# P01_mpsm.net
KiCad netlist of a schematic drawn in Altium Designer
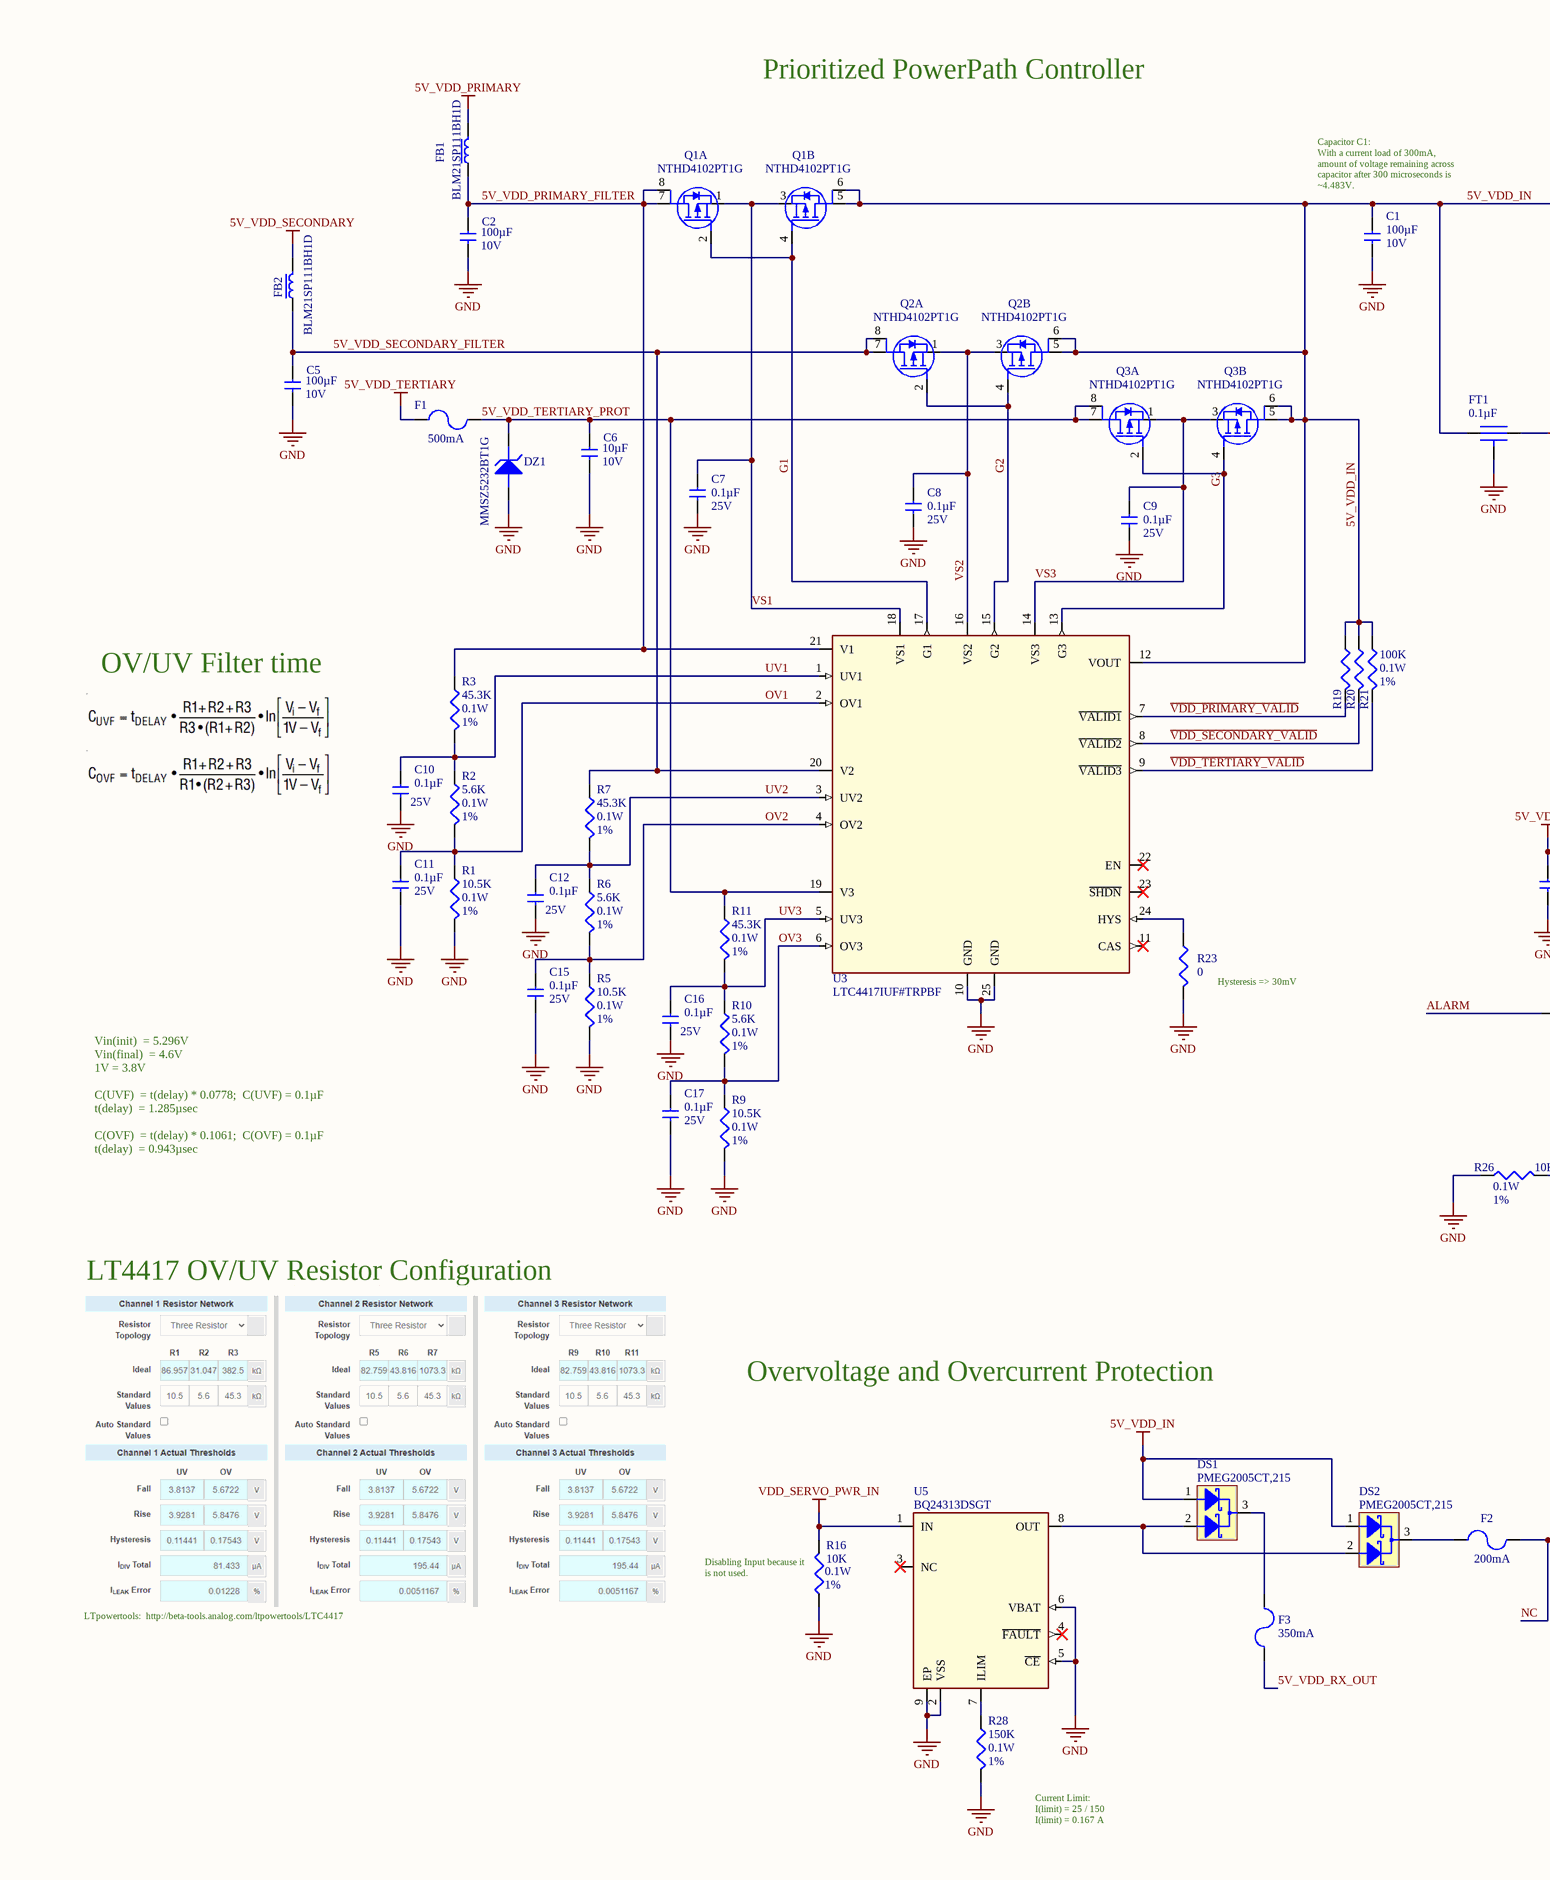
[diagram p0: P01_mpsm.SchDoc, left]
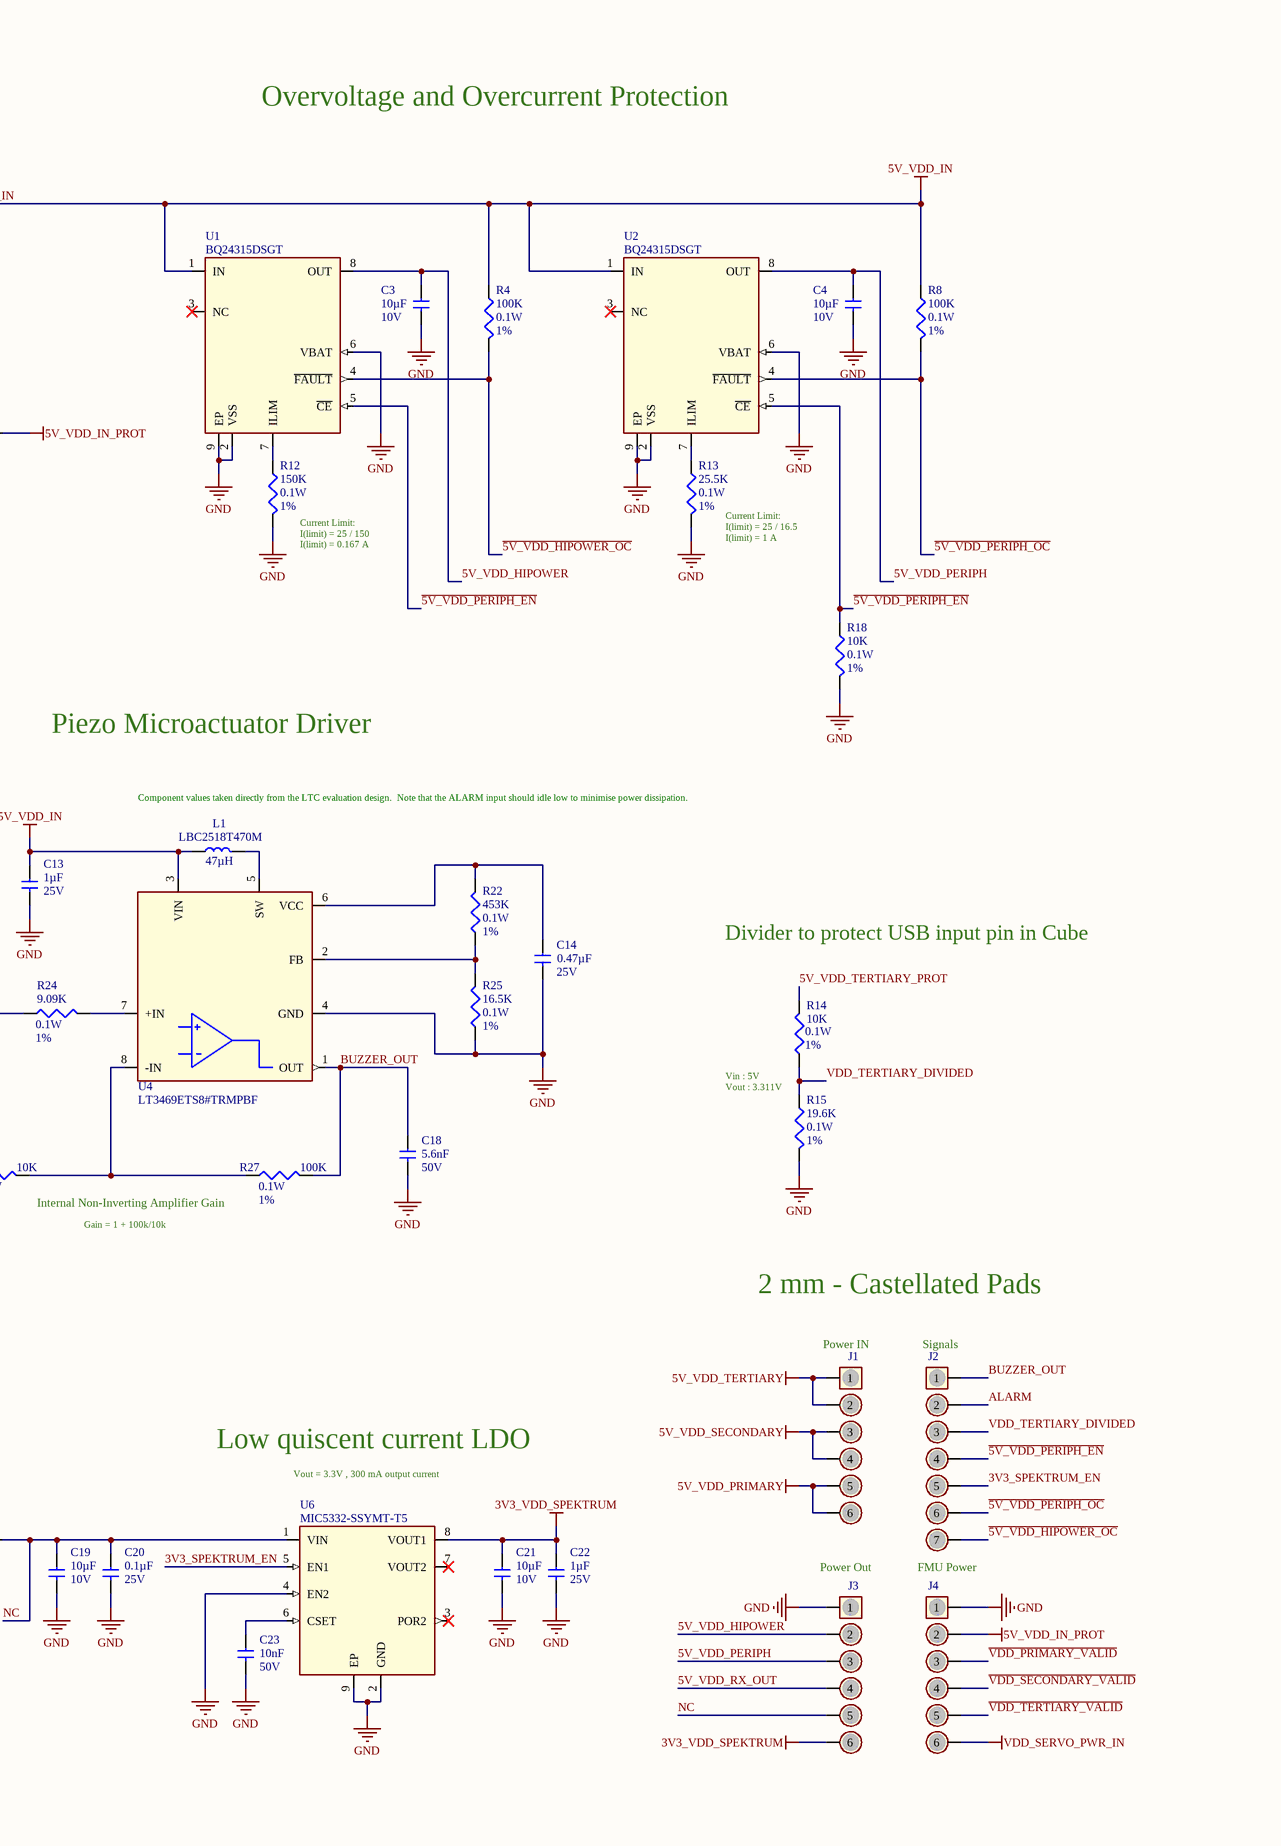
[diagram p1: P01_mpsm.SchDoc, right]

(export (version "E")
  (design (tool "Eeschema 10.0.6"))
  (components
    (comp (ref "C1")
      (value "100µF")
      (footprint "CC-1206")
      (fields
        (field (name "MFG") "TDK Corporation")
        (field (name "TOLERANCE") "20%")
        (field (name "VOLTAGE") "10V")
      )
      (libsource (lib "mpsm") (part "CC-100µF-X5R-10V-20%-1206"))
    )
    (comp (ref "C2")
      (value "100µF")
      (footprint "CC-1206")
      (fields
        (field (name "MFG") "TDK Corporation")
        (field (name "TOLERANCE") "20%")
        (field (name "VOLTAGE") "10V")
      )
      (libsource (lib "mpsm") (part "CC-100µF-X5R-10V-20%-1206"))
    )
    (comp (ref "C3")
      (value "10µF")
      (footprint "CC-0603")
      (fields
        (field (name "MFG") "Murata Electronics")
        (field (name "TOLERANCE") "10%")
        (field (name "VOLTAGE") "10V")
      )
      (libsource (lib "mpsm") (part "CC-10µF-X7T-10V-10%-0603"))
    )
    (comp (ref "C4")
      (value "10µF")
      (footprint "CC-0603")
      (fields
        (field (name "MFG") "Murata Electronics")
        (field (name "TOLERANCE") "10%")
        (field (name "VOLTAGE") "10V")
      )
      (libsource (lib "mpsm") (part "CC-10µF-X7T-10V-10%-0603"))
    )
    (comp (ref "C5")
      (value "100µF")
      (footprint "CC-1206")
      (fields
        (field (name "MFG") "TDK Corporation")
        (field (name "TOLERANCE") "20%")
        (field (name "VOLTAGE") "10V")
      )
      (libsource (lib "mpsm") (part "CC-100µF-X5R-10V-20%-1206"))
    )
    (comp (ref "C6")
      (value "10µF")
      (footprint "CC-0603")
      (fields
        (field (name "MFG") "Murata Electronics")
        (field (name "TOLERANCE") "10%")
        (field (name "VOLTAGE") "10V")
      )
      (libsource (lib "mpsm") (part "CC-10µF-X7T-10V-10%-0603"))
    )
    (comp (ref "C7")
      (value "0.1µF")
      (footprint "CC-0402")
      (fields
        (field (name "MFG") "Murata Electronics")
        (field (name "TOLERANCE") "10%")
        (field (name "VOLTAGE") "25V")
      )
      (libsource (lib "mpsm") (part "CC-0.1µF-X7R-25V-10%-0402"))
    )
    (comp (ref "C8")
      (value "0.1µF")
      (footprint "CC-0402")
      (fields
        (field (name "MFG") "Murata Electronics")
        (field (name "TOLERANCE") "10%")
        (field (name "VOLTAGE") "25V")
      )
      (libsource (lib "mpsm") (part "CC-0.1µF-X7R-25V-10%-0402"))
    )
    (comp (ref "C9")
      (value "0.1µF")
      (footprint "CC-0402")
      (fields
        (field (name "MFG") "Murata Electronics")
        (field (name "TOLERANCE") "10%")
        (field (name "VOLTAGE") "25V")
      )
      (libsource (lib "mpsm") (part "CC-0.1µF-X7R-25V-10%-0402"))
    )
    (comp (ref "C10")
      (value "0.1µF")
      (footprint "CC-0402")
      (fields
        (field (name "MFG") "Murata Electronics")
        (field (name "TOLERANCE") "10%")
        (field (name "VOLTAGE") "25V")
      )
      (libsource (lib "mpsm") (part "CC-0.1µF-X7R-25V-10%-0402"))
    )
    (comp (ref "C11")
      (value "0.1µF")
      (footprint "CC-0402")
      (fields
        (field (name "MFG") "Murata Electronics")
        (field (name "TOLERANCE") "10%")
        (field (name "VOLTAGE") "25V")
      )
      (libsource (lib "mpsm") (part "CC-0.1µF-X7R-25V-10%-0402"))
    )
    (comp (ref "C12")
      (value "0.1µF")
      (footprint "CC-0402")
      (fields
        (field (name "MFG") "Murata Electronics")
        (field (name "TOLERANCE") "10%")
        (field (name "VOLTAGE") "25V")
      )
      (libsource (lib "mpsm") (part "CC-0.1µF-X7R-25V-10%-0402"))
    )
    (comp (ref "C13")
      (value "1µF")
      (footprint "CC-0402")
      (fields
        (field (name "MFG") "Murata Electronics")
        (field (name "TOLERANCE") "10%")
        (field (name "VOLTAGE") "25V")
      )
      (libsource (lib "mpsm") (part "CC-1µF-X6S-25V-10%-0402"))
    )
    (comp (ref "C14")
      (value "0.47µF")
      (footprint "CC-0402")
      (fields
        (field (name "TOLERANCE") "±10%")
        (field (name "MFG") "Murata Electronics")
        (field (name "VOLTAGE") "25V")
      )
      (libsource (lib "mpsm") (part "CC-0.47µF-X5R-25V-10%-0402"))
    )
    (comp (ref "C15")
      (value "0.1µF")
      (footprint "CC-0402")
      (fields
        (field (name "MFG") "Murata Electronics")
        (field (name "TOLERANCE") "10%")
        (field (name "VOLTAGE") "25V")
      )
      (libsource (lib "mpsm") (part "CC-0.1µF-X7R-25V-10%-0402"))
    )
    (comp (ref "C16")
      (value "0.1µF")
      (footprint "CC-0402")
      (fields
        (field (name "MFG") "Murata Electronics")
        (field (name "TOLERANCE") "10%")
        (field (name "VOLTAGE") "25V")
      )
      (libsource (lib "mpsm") (part "CC-0.1µF-X7R-25V-10%-0402"))
    )
    (comp (ref "C17")
      (value "0.1µF")
      (footprint "CC-0402")
      (fields
        (field (name "MFG") "Murata Electronics")
        (field (name "TOLERANCE") "10%")
        (field (name "VOLTAGE") "25V")
      )
      (libsource (lib "mpsm") (part "CC-0.1µF-X7R-25V-10%-0402"))
    )
    (comp (ref "C18")
      (value "5.6nF")
      (footprint "CC-0402")
      (fields (field (name "TOLERANCE") "±10%") (field (name "MFG") "Yageo") (field (name "VOLTAGE") "50V"))
      (libsource (lib "mpsm") (part "CC-5.6nF-X7R-50V-5%-0402"))
    )
    (comp (ref "C19")
      (value "10µF")
      (footprint "CC-0603")
      (fields
        (field (name "MFG") "Murata Electronics")
        (field (name "TOLERANCE") "10%")
        (field (name "VOLTAGE") "10V")
      )
      (libsource (lib "mpsm") (part "CC-10µF-X7T-10V-10%-0603"))
    )
    (comp (ref "C20")
      (value "0.1µF")
      (footprint "CC-0402")
      (fields
        (field (name "MFG") "Murata Electronics")
        (field (name "TOLERANCE") "10%")
        (field (name "VOLTAGE") "25V")
      )
      (libsource (lib "mpsm") (part "CC-0.1µF-X7R-25V-10%-0402"))
    )
    (comp (ref "C21")
      (value "10µF")
      (footprint "CC-0603")
      (fields
        (field (name "MFG") "Murata Electronics")
        (field (name "TOLERANCE") "10%")
        (field (name "VOLTAGE") "10V")
      )
      (libsource (lib "mpsm") (part "CC-10µF-X7T-10V-10%-0603"))
    )
    (comp (ref "C22")
      (value "1µF")
      (footprint "CC-0402")
      (fields
        (field (name "MFG") "Murata Electronics")
        (field (name "TOLERANCE") "10%")
        (field (name "VOLTAGE") "25V")
      )
      (libsource (lib "mpsm") (part "CC-1µF-X6S-25V-10%-0402"))
    )
    (comp (ref "C23")
      (value "10nF")
      (footprint "CC-0402")
      (fields
        (field (name "TOLERANCE") "±10%")
        (field (name "MFG") "Murata Electronics")
        (field (name "VOLTAGE") "50V")
      )
      (libsource (lib "mpsm") (part "CC-10nF-X7R-50V-10%-0402"))
    )
    (comp (ref "DS1")
      (value "PMEG2005CT,215")
      (footprint "SOT-23-3")
      (fields (field (name "MFG") "Nexperia USA Inc."))
      (libsource (lib "mpsm") (part "DS-PMEG2005CT,215-SOT-23-3"))
    )
    (comp (ref "DS2")
      (value "PMEG2005CT,215")
      (footprint "SOT-23-3")
      (fields (field (name "MFG") "Nexperia USA Inc."))
      (libsource (lib "mpsm") (part "DS-PMEG2005CT,215-SOT-23-3"))
    )
    (comp (ref "DZ1")
      (value "MMSZ5232BT1G")
      (footprint "SOD-123")
      (fields (field (name "MFG") "ON Semiconductor"))
      (libsource (lib "mpsm") (part "DZ-5.6V-MMSZ5232BT1G-SOD-123"))
    )
    (comp (ref "F1")
      (value "500mA")
      (footprint "CF-0402")
      (fields (field (name "MFG") "BOURNS"))
      (libsource (lib "mpsm") (part "FUSE-500mA-32V-0402"))
    )
    (comp (ref "F2")
      (value "200mA")
      (footprint "CF-1206")
      (fields (field (name "MFG") "Bel Fuse Inc."))
      (libsource (lib "mpsm") (part "FUSE-200mA-20V-1206"))
    )
    (comp (ref "F3")
      (value "350mA")
      (footprint "CF-1206")
      (fields (field (name "MFG") "Littelfuse Inc."))
      (libsource (lib "mpsm") (part "FUSE-350mA-16V-1206"))
    )
    (comp (ref "FB1")
      (value "BLM21SP111BH1D")
      (footprint "FB-0805")
      (fields (field (name "MFG") "Murata Electronics"))
      (libsource (lib "mpsm") (part "FB-BLM21SP111BH1D-0805"))
    )
    (comp (ref "FB2")
      (value "BLM21SP111BH1D")
      (footprint "FB-0805")
      (fields (field (name "MFG") "Murata Electronics"))
      (libsource (lib "mpsm") (part "FB-BLM21SP111BH1D-0805"))
    )
    (comp (ref "FT1")
      (value "0.1µF")
      (footprint "CF-0603 - 3PC-PAD")
      (fields (field (name "MFG") "Murata Electronics"))
      (libsource (lib "mpsm") (part "CAP FT-0.1µF-X7R-16V-20%-0603"))
    )
    (comp (ref "J1")
      (value "6 Contacts")
      (footprint "1X06M")
      (fields
        (field (name "MANUFACTURER") "TE Connectivity Aerospace, Defense and Marine")
        (field (name "MANUFACTURER PART NUMBER") "205089-1")
      )
      (libsource (lib "mpsm") (part "6-Pin-Contact-PSM"))
    )
    (comp (ref "J2")
      (value "7 Contacts")
      (footprint "1X07M")
      (fields
        (field (name "MANUFACTURER") "TE Connectivity Aerospace, Defense and Marine")
        (field (name "MANUFACTURER PART NUMBER") "205089-1")
      )
      (libsource (lib "mpsm") (part "7-Pin-Contact-PSM"))
    )
    (comp (ref "J3")
      (value "6 Contacts")
      (footprint "1X06M")
      (fields
        (field (name "MANUFACTURER") "TE Connectivity Aerospace, Defense and Marine")
        (field (name "MANUFACTURER PART NUMBER") "205089-1")
      )
      (libsource (lib "mpsm") (part "6-Pin-Contact-PSM"))
    )
    (comp (ref "J4")
      (value "6 Contacts")
      (footprint "1X06M")
      (fields
        (field (name "MANUFACTURER") "TE Connectivity Aerospace, Defense and Marine")
        (field (name "MANUFACTURER PART NUMBER") "205089-1")
      )
      (libsource (lib "") (part "6-Pin-Contact-PSM_1"))
    )
    (comp (ref "L1")
      (value "LBC2518T470M")
      (footprint "IND-1007")
      (fields (field (name "MFG") "Taiyo Yuden") (field (name "INDUCTANCE") "47µH"))
      (libsource (lib "mpsm") (part "IND-47µH-165mA-1.9Ohm-1007"))
    )
    (comp (ref "Q1")
      (value "NTHD4102PT1G")
      (footprint "1206-8_8-SMD")
      (fields (field (name "MFG") "ON Semiconductor"))
      (libsource (lib "") (part "MOSFET-P 2CH-NTHD4102PT1G-8-SMD_1"))
    )
    (comp (ref "Q2")
      (value "NTHD4102PT1G")
      (footprint "1206-8_8-SMD")
      (fields (field (name "MFG") "ON Semiconductor"))
      (libsource (lib "mpsm") (part "MOSFET-P 2CH-NTHD4102PT1G-8-SMD"))
    )
    (comp (ref "Q3")
      (value "NTHD4102PT1G")
      (footprint "1206-8_8-SMD")
      (fields (field (name "MFG") "ON Semiconductor"))
      (libsource (lib "mpsm") (part "MOSFET-P 2CH-NTHD4102PT1G-8-SMD"))
    )
    (comp (ref "R1")
      (value "10.5K")
      (footprint "CR-0402")
      (fields
        (field (name "MFG") "Panasonic Electronic Components")
        (field (name "POWER") "0.1W")
        (field (name "TOLERANCE") "1%")
      )
      (libsource (lib "mpsm") (part "CR-10.5K-1/10W-1%-0402"))
    )
    (comp (ref "R2")
      (value "5.6K")
      (footprint "CR-0402")
      (fields
        (field (name "MFG") "Panasonic Electronic Components")
        (field (name "POWER") "0.1W")
        (field (name "TOLERANCE") "1%")
      )
      (libsource (lib "mpsm") (part "CR-5.6K-1/10W-1%-0402"))
    )
    (comp (ref "R3")
      (value "45.3K")
      (footprint "CR-0402")
      (fields
        (field (name "MFG") "Panasonic Electronic Components")
        (field (name "POWER") "0.1W")
        (field (name "TOLERANCE") "1%")
      )
      (libsource (lib "mpsm") (part "CR- 45.3K-1/10W-1%-0402"))
    )
    (comp (ref "R4")
      (value "100K")
      (footprint "CR-0402")
      (fields
        (field (name "MFG") "Panasonic Electronic Components")
        (field (name "POWER") "0.1W")
        (field (name "TOLERANCE") "1%")
      )
      (libsource (lib "mpsm") (part "CR-100K-1/10W-1%-0402"))
    )
    (comp (ref "R5")
      (value "10.5K")
      (footprint "CR-0402")
      (fields
        (field (name "MFG") "Panasonic Electronic Components")
        (field (name "POWER") "0.1W")
        (field (name "TOLERANCE") "1%")
      )
      (libsource (lib "mpsm") (part "CR-10.5K-1/10W-1%-0402"))
    )
    (comp (ref "R6")
      (value "5.6K")
      (footprint "CR-0402")
      (fields
        (field (name "MFG") "Panasonic Electronic Components")
        (field (name "POWER") "0.1W")
        (field (name "TOLERANCE") "1%")
      )
      (libsource (lib "mpsm") (part "CR-5.6K-1/10W-1%-0402"))
    )
    (comp (ref "R7")
      (value "45.3K")
      (footprint "CR-0402")
      (fields
        (field (name "MFG") "Panasonic Electronic Components")
        (field (name "POWER") "0.1W")
        (field (name "TOLERANCE") "1%")
      )
      (libsource (lib "mpsm") (part "CR- 45.3K-1/10W-1%-0402"))
    )
    (comp (ref "R8")
      (value "100K")
      (footprint "CR-0402")
      (fields
        (field (name "MFG") "Panasonic Electronic Components")
        (field (name "POWER") "0.1W")
        (field (name "TOLERANCE") "1%")
      )
      (libsource (lib "mpsm") (part "CR-100K-1/10W-1%-0402"))
    )
    (comp (ref "R9")
      (value "10.5K")
      (footprint "CR-0402")
      (fields
        (field (name "MFG") "Panasonic Electronic Components")
        (field (name "POWER") "0.1W")
        (field (name "TOLERANCE") "1%")
      )
      (libsource (lib "mpsm") (part "CR-10.5K-1/10W-1%-0402"))
    )
    (comp (ref "R10")
      (value "5.6K")
      (footprint "CR-0402")
      (fields
        (field (name "MFG") "Panasonic Electronic Components")
        (field (name "POWER") "0.1W")
        (field (name "TOLERANCE") "1%")
      )
      (libsource (lib "mpsm") (part "CR-5.6K-1/10W-1%-0402"))
    )
    (comp (ref "R11")
      (value "45.3K")
      (footprint "CR-0402")
      (fields
        (field (name "MFG") "Panasonic Electronic Components")
        (field (name "POWER") "0.1W")
        (field (name "TOLERANCE") "1%")
      )
      (libsource (lib "mpsm") (part "CR- 45.3K-1/10W-1%-0402"))
    )
    (comp (ref "R12")
      (value "150K")
      (footprint "CR-0402")
      (fields
        (field (name "MFG") "Panasonic Electronic Components")
        (field (name "POWER") "0.1W")
        (field (name "TOLERANCE") "1%")
      )
      (libsource (lib "mpsm") (part "CR-150K-1/10W-1%-0402"))
    )
    (comp (ref "R13")
      (value "25.5K")
      (footprint "CR-0402")
      (fields
        (field (name "MFG") "Panasonic Electronic Components")
        (field (name "POWER") "0.1W")
        (field (name "TOLERANCE") "1%")
      )
      (libsource (lib "mpsm") (part "CR-25.5K-1/10W-1%-0402"))
    )
    (comp (ref "R14")
      (value "10K")
      (footprint "CR-0402")
      (fields
        (field (name "MFG") "Panasonic Electronic Components")
        (field (name "POWER") "0.1W")
        (field (name "TOLERANCE") "1%")
      )
      (libsource (lib "mpsm") (part "CR-10K-1/10W-1%-0402"))
    )
    (comp (ref "R15")
      (value "19.6K")
      (footprint "CR-0402")
      (fields
        (field (name "MFG") "Panasonic Electronic Components")
        (field (name "POWER") "0.1W")
        (field (name "TOLERANCE") "1%")
      )
      (libsource (lib "mpsm") (part "CR-19.6K-1/10W-1%-0402"))
    )
    (comp (ref "R16")
      (value "10K")
      (footprint "CR-0402")
      (fields
        (field (name "MFG") "Panasonic Electronic Components")
        (field (name "POWER") "0.1W")
        (field (name "TOLERANCE") "1%")
      )
      (libsource (lib "mpsm") (part "CR-10K-1/10W-1%-0402"))
    )
    (comp (ref "R18")
      (value "10K")
      (footprint "CR-0402")
      (fields
        (field (name "MFG") "Panasonic Electronic Components")
        (field (name "POWER") "0.1W")
        (field (name "TOLERANCE") "1%")
      )
      (libsource (lib "mpsm") (part "CR-10K-1/10W-1%-0402"))
    )
    (comp (ref "R19")
      (value "100K")
      (footprint "CR-0402")
      (fields
        (field (name "MFG") "Panasonic Electronic Components")
        (field (name "POWER") "0.1W")
        (field (name "TOLERANCE") "1%")
      )
      (libsource (lib "mpsm") (part "CR-100K-1/10W-1%-0402"))
    )
    (comp (ref "R20")
      (value "100K")
      (footprint "CR-0402")
      (fields
        (field (name "MFG") "Panasonic Electronic Components")
        (field (name "POWER") "0.1W")
        (field (name "TOLERANCE") "1%")
      )
      (libsource (lib "mpsm") (part "CR-100K-1/10W-1%-0402"))
    )
    (comp (ref "R21")
      (value "100K")
      (footprint "CR-0402")
      (fields
        (field (name "MFG") "Panasonic Electronic Components")
        (field (name "POWER") "0.1W")
        (field (name "TOLERANCE") "1%")
      )
      (libsource (lib "mpsm") (part "CR-100K-1/10W-1%-0402"))
    )
    (comp (ref "R22")
      (value "453K")
      (footprint "CR-0402")
      (fields
        (field (name "MFG") "Panasonic Electronic Components")
        (field (name "POWER") "0.1W")
        (field (name "TOLERANCE") "1%")
      )
      (libsource (lib "mpsm") (part "CR- 453K-1/10W-1%-0402"))
    )
    (comp (ref "R23")
      (value "0")
      (footprint "CR-0402")
      (fields
        (field (name "MFG") "Panasonic Electronic Components")
        (field (name "TOLERANCE") "1%")
        (field (name "POWER") "0.1W")
      )
      (libsource (lib "mpsm") (part "CR-0.0-1/10W-1%-0402"))
    )
    (comp (ref "R24")
      (value "9.09K")
      (footprint "CR-0402")
      (fields
        (field (name "MFG") "Panasonic Electronic Components")
        (field (name "POWER") "0.1W")
        (field (name "TOLERANCE") "1%")
      )
      (libsource (lib "mpsm") (part "CR-9.09K-1/10W-1%-0402"))
    )
    (comp (ref "R25")
      (value "16.5K")
      (footprint "CR-0402")
      (fields
        (field (name "MFG") "Panasonic Electronic Components")
        (field (name "POWER") "0.1W")
        (field (name "TOLERANCE") "1%")
      )
      (libsource (lib "mpsm") (part "CR-16.5K-1/10W-1%-0402"))
    )
    (comp (ref "R26")
      (value "10K")
      (footprint "CR-0402")
      (fields
        (field (name "MFG") "Panasonic Electronic Components")
        (field (name "POWER") "0.1W")
        (field (name "TOLERANCE") "1%")
      )
      (libsource (lib "mpsm") (part "CR-10K-1/10W-1%-0402"))
    )
    (comp (ref "R27")
      (value "100K")
      (footprint "CR-0402")
      (fields
        (field (name "MFG") "Panasonic Electronic Components")
        (field (name "POWER") "0.1W")
        (field (name "TOLERANCE") "1%")
      )
      (libsource (lib "mpsm") (part "CR-100K-1/10W-1%-0402"))
    )
    (comp (ref "R28")
      (value "150K")
      (footprint "CR-0402")
      (fields
        (field (name "MFG") "Panasonic Electronic Components")
        (field (name "POWER") "0.1W")
        (field (name "TOLERANCE") "1%")
      )
      (libsource (lib "mpsm") (part "CR-150K-1/10W-1%-0402"))
    )
    (comp (ref "U1")
      (value "BQ24315DSGT")
      (footprint "8-WFDFN_2x2")
      (fields (field (name "MFG") "Texas Instruments"))
      (libsource (lib "mpsm") (part "IC-BQ24315DSGT-8-WFDFN"))
    )
    (comp (ref "U2")
      (value "BQ24315DSGT")
      (footprint "8-WFDFN_2x2")
      (fields (field (name "MFG") "Texas Instruments"))
      (libsource (lib "mpsm") (part "IC-BQ24315DSGT-8-WFDFN"))
    )
    (comp (ref "U3")
      (value "LTC4417IUF#TRPBF")
      (footprint "mpsm:QFN-24_2x2")
      (fields (field (name "MFG") "Analog Devices Inc."))
      (libsource (lib "mpsm") (part "IC-LTC4417IUF-24-QFN"))
    )
    (comp (ref "U4")
      (value "LT3469ETS8#TRMPBF")
      (footprint "mpsm:SOT-23-8")
      (fields (field (name "MFG") "Analog Devices Inc."))
      (libsource (lib "mpsm") (part "IC-LT3469ETS8-TSOT-23-8"))
    )
    (comp (ref "U5")
      (value "BQ24313DSGT")
      (footprint "8-WFDFN_2x2")
      (fields (field (name "MFG") "Texas Instruments"))
      (libsource (lib "mpsm") (part "IC-BQ24313DSGT-8-WFDFN"))
    )
    (comp (ref "U6")
      (value "MIC5332-SSYMT-T5")
      (footprint "MLF-8_2x2")
      (fields (field (name "MFG") "Microchip Technology"))
      (libsource (lib "mpsm") (part "IC-MIC5332-8-MLF"))
    )
  )
  (nets
    (net (code "1") (name "/3V3_SPEKTRUM_EN") (class "Default")
      (node (ref "J2") (pin "5") (pinfunction "5_5") (pintype "passive"))
      (node (ref "U6") (pin "5") (pinfunction "EN1_5") (pintype "input"))
    )
    (net (code "2") (name "/5V_VDD_HIPOWER") (class "Default")
      (node (ref "C3") (pin "1") (pinfunction "1_1") (pintype "passive"))
      (node (ref "J3") (pin "2") (pinfunction "2_2") (pintype "passive"))
      (node (ref "U1") (pin "8") (pinfunction "OUT_8") (pintype "power_in"))
    )
    (net (code "3") (name "/5V_VDD_PERIPH") (class "Default")
      (node (ref "C4") (pin "1") (pinfunction "1_1") (pintype "passive"))
      (node (ref "J3") (pin "3") (pinfunction "3_3") (pintype "passive"))
      (node (ref "U2") (pin "8") (pinfunction "OUT_8") (pintype "power_in"))
    )
    (net (code "4") (name "/5V_VDD_PRIMARY_FILTER") (class "Default")
      (node (ref "C2") (pin "1") (pinfunction "1_1") (pintype "passive"))
      (node (ref "FB1") (pin "1") (pinfunction "1_1") (pintype "passive"))
      (node (ref "Q1") (pin "7") (pinfunction "D1_7") (pintype "passive"))
      (node (ref "Q1") (pin "8") (pinfunction "D1_8") (pintype "passive"))
      (node (ref "R3") (pin "1") (pinfunction "1_1") (pintype "passive"))
      (node (ref "U3") (pin "21") (pinfunction "V1_21") (pintype "power_in"))
    )
    (net (code "5") (name "/5V_VDD_RX_OUT") (class "Default")
      (node (ref "F3") (pin "1") (pinfunction "1_1") (pintype "passive"))
      (node (ref "J3") (pin "4") (pinfunction "4_4") (pintype "passive"))
    )
    (net (code "6") (name "/5V_VDD_SECONDARY_FILTER") (class "Default")
      (node (ref "C5") (pin "1") (pinfunction "1_1") (pintype "passive"))
      (node (ref "FB2") (pin "1") (pinfunction "1_1") (pintype "passive"))
      (node (ref "Q2") (pin "7") (pinfunction "D1_7") (pintype "passive"))
      (node (ref "Q2") (pin "8") (pinfunction "D1_8") (pintype "passive"))
      (node (ref "R7") (pin "1") (pinfunction "1_1") (pintype "passive"))
      (node (ref "U3") (pin "20") (pinfunction "V2_20") (pintype "power_in"))
    )
    (net (code "7") (name "/5V_VDD_TERTIARY_PROT") (class "Default")
      (node (ref "C6") (pin "1") (pinfunction "1_1") (pintype "passive"))
      (node (ref "DZ1") (pin "K") (pinfunction "K_K") (pintype "passive"))
      (node (ref "F1") (pin "1") (pinfunction "POS_1") (pintype "passive"))
      (node (ref "Q3") (pin "7") (pinfunction "D1_7") (pintype "passive"))
      (node (ref "Q3") (pin "8") (pinfunction "D1_8") (pintype "passive"))
      (node (ref "R11") (pin "1") (pinfunction "1_1") (pintype "passive"))
      (node (ref "R14") (pin "2") (pinfunction "2_2") (pintype "passive"))
      (node (ref "U3") (pin "19") (pinfunction "V3_19") (pintype "power_in"))
    )
    (net (code "8") (name "/ALARM") (class "Default")
      (node (ref "J2") (pin "2") (pinfunction "2_2") (pintype "passive"))
      (node (ref "R24") (pin "1") (pinfunction "1_1") (pintype "passive"))
    )
    (net (code "9") (name "/BUZZER_OUT") (class "Default")
      (node (ref "C18") (pin "1") (pinfunction "1_1") (pintype "passive"))
      (node (ref "J2") (pin "1") (pinfunction "1_1") (pintype "passive"))
      (node (ref "R27") (pin "2") (pinfunction "2_2") (pintype "passive"))
      (node (ref "U4") (pin "1") (pinfunction "OUT_1") (pintype "output"))
    )
    (net (code "10") (name "/G1") (class "Default")
      (node (ref "Q1") (pin "2") (pinfunction "G1_2") (pintype "passive"))
      (node (ref "Q1") (pin "4") (pinfunction "G2_4") (pintype "passive"))
      (node (ref "U3") (pin "17") (pinfunction "G1_17") (pintype "output"))
    )
    (net (code "11") (name "/G2") (class "Default")
      (node (ref "Q2") (pin "2") (pinfunction "G1_2") (pintype "passive"))
      (node (ref "Q2") (pin "4") (pinfunction "G2_4") (pintype "passive"))
      (node (ref "U3") (pin "15") (pinfunction "G2_15") (pintype "output"))
    )
    (net (code "12") (name "/G3") (class "Default")
      (node (ref "Q3") (pin "2") (pinfunction "G1_2") (pintype "passive"))
      (node (ref "Q3") (pin "4") (pinfunction "G2_4") (pintype "passive"))
      (node (ref "U3") (pin "13") (pinfunction "G3_13") (pintype "output"))
    )
    (net (code "13") (name "/NC") (class "Default")
      (node (ref "C19") (pin "1") (pinfunction "1_1") (pintype "passive"))
      (node (ref "C20") (pin "1") (pinfunction "1_1") (pintype "passive"))
      (node (ref "F2") (pin "2") (pinfunction "2_2") (pintype "passive"))
      (node (ref "J3") (pin "5") (pinfunction "5_5") (pintype "passive"))
      (node (ref "U6") (pin "1") (pinfunction "VIN_1") (pintype "power_in"))
    )
    (net (code "14") (name "/OV1") (class "Default")
      (node (ref "C11") (pin "1") (pinfunction "1_1") (pintype "passive"))
      (node (ref "R1") (pin "1") (pinfunction "1_1") (pintype "passive"))
      (node (ref "R2") (pin "2") (pinfunction "2_2") (pintype "passive"))
      (node (ref "U3") (pin "2") (pinfunction "OV1_2") (pintype "input"))
    )
    (net (code "15") (name "/OV2") (class "Default")
      (node (ref "C15") (pin "1") (pinfunction "1_1") (pintype "passive"))
      (node (ref "R5") (pin "1") (pinfunction "1_1") (pintype "passive"))
      (node (ref "R6") (pin "2") (pinfunction "2_2") (pintype "passive"))
      (node (ref "U3") (pin "4") (pinfunction "OV2_4") (pintype "input"))
    )
    (net (code "16") (name "/OV3") (class "Default")
      (node (ref "C17") (pin "1") (pinfunction "1_1") (pintype "passive"))
      (node (ref "R10") (pin "2") (pinfunction "2_2") (pintype "passive"))
      (node (ref "R9") (pin "1") (pinfunction "1_1") (pintype "passive"))
      (node (ref "U3") (pin "6") (pinfunction "OV3_6") (pintype "input"))
    )
    (net (code "17") (name "/UV1") (class "Default")
      (node (ref "C10") (pin "1") (pinfunction "1_1") (pintype "passive"))
      (node (ref "R2") (pin "1") (pinfunction "1_1") (pintype "passive"))
      (node (ref "R3") (pin "2") (pinfunction "2_2") (pintype "passive"))
      (node (ref "U3") (pin "1") (pinfunction "UV1_1") (pintype "input"))
    )
    (net (code "18") (name "/UV2") (class "Default")
      (node (ref "C12") (pin "1") (pinfunction "1_1") (pintype "passive"))
      (node (ref "R6") (pin "1") (pinfunction "1_1") (pintype "passive"))
      (node (ref "R7") (pin "2") (pinfunction "2_2") (pintype "passive"))
      (node (ref "U3") (pin "3") (pinfunction "UV2_3") (pintype "input"))
    )
    (net (code "19") (name "/UV3") (class "Default")
      (node (ref "C16") (pin "1") (pinfunction "1_1") (pintype "passive"))
      (node (ref "R10") (pin "1") (pinfunction "1_1") (pintype "passive"))
      (node (ref "R11") (pin "2") (pinfunction "2_2") (pintype "passive"))
      (node (ref "U3") (pin "5") (pinfunction "UV3_5") (pintype "input"))
    )
    (net (code "20") (name "/VDD_TERTIARY_DIVIDED") (class "Default")
      (node (ref "J2") (pin "3") (pinfunction "3_3") (pintype "passive"))
      (node (ref "R14") (pin "1") (pinfunction "1_1") (pintype "passive"))
      (node (ref "R15") (pin "1") (pinfunction "1_1") (pintype "passive"))
    )
    (net (code "21") (name "/VS1") (class "Default")
      (node (ref "C7") (pin "1") (pinfunction "1_1") (pintype "passive"))
      (node (ref "Q1") (pin "1") (pinfunction "S1_1") (pintype "passive"))
      (node (ref "Q1") (pin "3") (pinfunction "S2_3") (pintype "passive"))
      (node (ref "U3") (pin "18") (pinfunction "VS1_18") (pintype "power_in"))
    )
    (net (code "22") (name "/VS2") (class "Default")
      (node (ref "C8") (pin "1") (pinfunction "1_1") (pintype "passive"))
      (node (ref "Q2") (pin "1") (pinfunction "S1_1") (pintype "passive"))
      (node (ref "Q2") (pin "3") (pinfunction "S2_3") (pintype "passive"))
      (node (ref "U3") (pin "16") (pinfunction "VS2_16") (pintype "power_in"))
    )
    (net (code "23") (name "/VS3") (class "Default")
      (node (ref "C9") (pin "1") (pinfunction "1_1") (pintype "passive"))
      (node (ref "Q3") (pin "1") (pinfunction "S1_1") (pintype "passive"))
      (node (ref "Q3") (pin "3") (pinfunction "S2_3") (pintype "passive"))
      (node (ref "U3") (pin "14") (pinfunction "VS3_14") (pintype "power_in"))
    )
    (net (code "24") (name "/~{5V_VDD_HIPOWER_OC}") (class "Default")
      (node (ref "J2") (pin "7") (pinfunction "7_7") (pintype "passive"))
      (node (ref "R4") (pin "2") (pinfunction "2_2") (pintype "passive"))
      (node (ref "U1") (pin "4") (pinfunction "~{FAULT}_4") (pintype "output"))
    )
    (net (code "25") (name "/~{5V_VDD_PERIPH_EN}") (class "Default")
      (node (ref "J2") (pin "4") (pinfunction "4_4") (pintype "passive"))
      (node (ref "R18") (pin "1") (pinfunction "1_1") (pintype "passive"))
      (node (ref "U1") (pin "5") (pinfunction "~{CE}_5") (pintype "input"))
      (node (ref "U2") (pin "5") (pinfunction "~{CE}_5") (pintype "input"))
    )
    (net (code "26") (name "/~{5V_VDD_PERIPH_OC}") (class "Default")
      (node (ref "J2") (pin "6") (pinfunction "6_6") (pintype "passive"))
      (node (ref "R8") (pin "2") (pinfunction "2_2") (pintype "passive"))
      (node (ref "U2") (pin "4") (pinfunction "~{FAULT}_4") (pintype "output"))
    )
    (net (code "27") (name "/~{VDD_PRIMARY_VALID}") (class "Default")
      (node (ref "J4") (pin "3") (pinfunction "3_3") (pintype "passive"))
      (node (ref "R19") (pin "2") (pinfunction "2_2") (pintype "passive"))
      (node (ref "U3") (pin "7") (pinfunction "~{VALID1}_7") (pintype "output"))
    )
    (net (code "28") (name "/~{VDD_SECONDARY_VALID}") (class "Default")
      (node (ref "J4") (pin "4") (pinfunction "4_4") (pintype "passive"))
      (node (ref "R20") (pin "2") (pinfunction "2_2") (pintype "passive"))
      (node (ref "U3") (pin "8") (pinfunction "~{VALID2}_8") (pintype "output"))
    )
    (net (code "29") (name "/~{VDD_TERTIARY_VALID}") (class "Default")
      (node (ref "J4") (pin "5") (pinfunction "5_5") (pintype "passive"))
      (node (ref "R21") (pin "2") (pinfunction "2_2") (pintype "passive"))
      (node (ref "U3") (pin "9") (pinfunction "~{VALID3}_9") (pintype "output"))
    )
    (net (code "30") (name "3V3_VDD_SPEKTRUM") (class "Default")
      (node (ref "C21") (pin "1") (pinfunction "1_1") (pintype "passive"))
      (node (ref "C22") (pin "1") (pinfunction "1_1") (pintype "passive"))
      (node (ref "J3") (pin "6") (pinfunction "6_6") (pintype "passive"))
      (node (ref "U6") (pin "8") (pinfunction "VOUT1_8") (pintype "power_in"))
    )
    (net (code "31") (name "5V_VDD_IN") (class "Default")
      (node (ref "C1") (pin "1") (pinfunction "1_1") (pintype "passive"))
      (node (ref "C13") (pin "1") (pinfunction "1_1") (pintype "passive"))
      (node (ref "DS1") (pin "1") (pinfunction "A1_1") (pintype "passive"))
      (node (ref "DS2") (pin "1") (pinfunction "A1_1") (pintype "passive"))
      (node (ref "FT1") (pin "1") (pinfunction "1_1") (pintype "passive"))
      (node (ref "L1") (pin "1") (pinfunction "1_1") (pintype "passive"))
      (node (ref "Q1") (pin "5") (pinfunction "D2_5") (pintype "passive"))
      (node (ref "Q1") (pin "6") (pinfunction "D2_6") (pintype "passive"))
      (node (ref "Q2") (pin "5") (pinfunction "D2_5") (pintype "passive"))
      (node (ref "Q2") (pin "6") (pinfunction "D2_6") (pintype "passive"))
      (node (ref "Q3") (pin "5") (pinfunction "D2_5") (pintype "passive"))
      (node (ref "Q3") (pin "6") (pinfunction "D2_6") (pintype "passive"))
      (node (ref "R19") (pin "1") (pinfunction "1_1") (pintype "passive"))
      (node (ref "R20") (pin "1") (pinfunction "1_1") (pintype "passive"))
      (node (ref "R21") (pin "1") (pinfunction "1_1") (pintype "passive"))
      (node (ref "R4") (pin "1") (pinfunction "1_1") (pintype "passive"))
      (node (ref "R8") (pin "1") (pinfunction "1_1") (pintype "passive"))
      (node (ref "U1") (pin "1") (pinfunction "IN_1") (pintype "power_in"))
      (node (ref "U2") (pin "1") (pinfunction "IN_1") (pintype "power_in"))
      (node (ref "U3") (pin "12") (pinfunction "VOUT_12") (pintype "power_in"))
      (node (ref "U4") (pin "3") (pinfunction "VIN_3") (pintype "power_in"))
    )
    (net (code "32") (name "5V_VDD_IN_PROT") (class "Default")
      (node (ref "FT1") (pin "2") (pinfunction "2_2") (pintype "passive"))
      (node (ref "J4") (pin "2") (pinfunction "2_2") (pintype "passive"))
    )
    (net (code "33") (name "5V_VDD_PRIMARY") (class "Default")
      (node (ref "FB1") (pin "2") (pinfunction "2_2") (pintype "passive"))
      (node (ref "J1") (pin "5") (pinfunction "5_5") (pintype "passive"))
      (node (ref "J1") (pin "6") (pinfunction "6_6") (pintype "passive"))
    )
    (net (code "34") (name "5V_VDD_SECONDARY") (class "Default")
      (node (ref "FB2") (pin "2") (pinfunction "2_2") (pintype "passive"))
      (node (ref "J1") (pin "3") (pinfunction "3_3") (pintype "passive"))
      (node (ref "J1") (pin "4") (pinfunction "4_4") (pintype "passive"))
    )
    (net (code "35") (name "5V_VDD_TERTIARY") (class "Default")
      (node (ref "F1") (pin "2") (pinfunction "NEG_2") (pintype "passive"))
      (node (ref "J1") (pin "1") (pinfunction "1_1") (pintype "passive"))
      (node (ref "J1") (pin "2") (pinfunction "2_2") (pintype "passive"))
    )
    (net (code "36") (name "GND") (class "Default")
      (node (ref "C1") (pin "2") (pinfunction "2_2") (pintype "passive"))
      (node (ref "C10") (pin "2") (pinfunction "2_2") (pintype "passive"))
      (node (ref "C11") (pin "2") (pinfunction "2_2") (pintype "passive"))
      (node (ref "C12") (pin "2") (pinfunction "2_2") (pintype "passive"))
      (node (ref "C13") (pin "2") (pinfunction "2_2") (pintype "passive"))
      (node (ref "C14") (pin "2") (pinfunction "2_2") (pintype "passive"))
      (node (ref "C15") (pin "2") (pinfunction "2_2") (pintype "passive"))
      (node (ref "C16") (pin "2") (pinfunction "2_2") (pintype "passive"))
      (node (ref "C17") (pin "2") (pinfunction "2_2") (pintype "passive"))
      (node (ref "C18") (pin "2") (pinfunction "2_2") (pintype "passive"))
      (node (ref "C19") (pin "2") (pinfunction "2_2") (pintype "passive"))
      (node (ref "C2") (pin "2") (pinfunction "2_2") (pintype "passive"))
      (node (ref "C20") (pin "2") (pinfunction "2_2") (pintype "passive"))
      (node (ref "C21") (pin "2") (pinfunction "2_2") (pintype "passive"))
      (node (ref "C22") (pin "2") (pinfunction "2_2") (pintype "passive"))
      (node (ref "C23") (pin "2") (pinfunction "2_2") (pintype "passive"))
      (node (ref "C3") (pin "2") (pinfunction "2_2") (pintype "passive"))
      (node (ref "C4") (pin "2") (pinfunction "2_2") (pintype "passive"))
      (node (ref "C5") (pin "2") (pinfunction "2_2") (pintype "passive"))
      (node (ref "C6") (pin "2") (pinfunction "2_2") (pintype "passive"))
      (node (ref "C7") (pin "2") (pinfunction "2_2") (pintype "passive"))
      (node (ref "C8") (pin "2") (pinfunction "2_2") (pintype "passive"))
      (node (ref "C9") (pin "2") (pinfunction "2_2") (pintype "passive"))
      (node (ref "DZ1") (pin "A") (pinfunction "A_A") (pintype "passive"))
      (node (ref "FT1") (pin "GND") (pinfunction "GND_GND") (pintype "passive"))
      (node (ref "J3") (pin "1") (pinfunction "1_1") (pintype "passive"))
      (node (ref "J4") (pin "1") (pinfunction "1_1") (pintype "passive"))
      (node (ref "R1") (pin "2") (pinfunction "2_2") (pintype "passive"))
      (node (ref "R12") (pin "2") (pinfunction "2_2") (pintype "passive"))
      (node (ref "R13") (pin "2") (pinfunction "2_2") (pintype "passive"))
      (node (ref "R15") (pin "2") (pinfunction "2_2") (pintype "passive"))
      (node (ref "R16") (pin "1") (pinfunction "1_1") (pintype "passive"))
      (node (ref "R18") (pin "2") (pinfunction "2_2") (pintype "passive"))
      (node (ref "R23") (pin "2") (pinfunction "2_2") (pintype "passive"))
      (node (ref "R25") (pin "1") (pinfunction "1_1") (pintype "passive"))
      (node (ref "R26") (pin "1") (pinfunction "1_1") (pintype "passive"))
      (node (ref "R28") (pin "2") (pinfunction "2_2") (pintype "passive"))
      (node (ref "R5") (pin "2") (pinfunction "2_2") (pintype "passive"))
      (node (ref "R9") (pin "2") (pinfunction "2_2") (pintype "passive"))
      (node (ref "U1") (pin "2") (pinfunction "VSS_2") (pintype "power_in"))
      (node (ref "U1") (pin "6") (pinfunction "VBAT_6") (pintype "input"))
      (node (ref "U1") (pin "9") (pinfunction "EP_9") (pintype "passive"))
      (node (ref "U2") (pin "2") (pinfunction "VSS_2") (pintype "power_in"))
      (node (ref "U2") (pin "6") (pinfunction "VBAT_6") (pintype "input"))
      (node (ref "U2") (pin "9") (pinfunction "EP_9") (pintype "passive"))
      (node (ref "U3") (pin "10") (pinfunction "GND_10") (pintype "power_in"))
      (node (ref "U3") (pin "25") (pinfunction "GND_25") (pintype "power_in"))
      (node (ref "U4") (pin "4") (pinfunction "GND_4") (pintype "power_in"))
      (node (ref "U5") (pin "2") (pinfunction "VSS_2") (pintype "power_in"))
      (node (ref "U5") (pin "5") (pinfunction "~{CE}_5") (pintype "input"))
      (node (ref "U5") (pin "6") (pinfunction "VBAT_6") (pintype "input"))
      (node (ref "U5") (pin "9") (pinfunction "EP_9") (pintype "passive"))
      (node (ref "U6") (pin "2") (pinfunction "GND_2") (pintype "power_in"))
      (node (ref "U6") (pin "4") (pinfunction "EN2_4") (pintype "input"))
      (node (ref "U6") (pin "9") (pinfunction "EP_9") (pintype "power_in"))
    )
    (net (code "37") (name "Net-(DS1-A2)") (class "Default")
      (node (ref "DS1") (pin "2") (pinfunction "A2_2") (pintype "passive"))
      (node (ref "DS2") (pin "2") (pinfunction "A2_2") (pintype "passive"))
      (node (ref "U5") (pin "8") (pinfunction "OUT_8") (pintype "power_in"))
    )
    (net (code "38") (name "Net-(DS1-C)") (class "Default")
      (node (ref "DS1") (pin "3") (pinfunction "C_3") (pintype "passive"))
      (node (ref "F3") (pin "2") (pinfunction "2_2") (pintype "passive"))
    )
    (net (code "39") (name "Net-(DS2-C)") (class "Default")
      (node (ref "DS2") (pin "3") (pinfunction "C_3") (pintype "passive"))
      (node (ref "F2") (pin "1") (pinfunction "1_1") (pintype "passive"))
    )
    (net (code "40") (name "Net-(U1-ILIM)") (class "Default")
      (node (ref "R12") (pin "1") (pinfunction "1_1") (pintype "passive"))
      (node (ref "U1") (pin "7") (pinfunction "ILIM_7") (pintype "bidirectional"))
    )
    (net (code "41") (name "Net-(U2-ILIM)") (class "Default")
      (node (ref "R13") (pin "1") (pinfunction "1_1") (pintype "passive"))
      (node (ref "U2") (pin "7") (pinfunction "ILIM_7") (pintype "bidirectional"))
    )
    (net (code "42") (name "Net-(U3-HYS)") (class "Default")
      (node (ref "R23") (pin "1") (pinfunction "1_1") (pintype "passive"))
      (node (ref "U3") (pin "24") (pinfunction "HYS_24") (pintype "input"))
    )
    (net (code "43") (name "Net-(U4-+IN)") (class "Default")
      (node (ref "R24") (pin "2") (pinfunction "2_2") (pintype "passive"))
      (node (ref "U4") (pin "7") (pinfunction "+IN_7") (pintype "passive"))
    )
    (net (code "44") (name "Net-(U4--IN)") (class "Default")
      (node (ref "R26") (pin "2") (pinfunction "2_2") (pintype "passive"))
      (node (ref "R27") (pin "1") (pinfunction "1_1") (pintype "passive"))
      (node (ref "U4") (pin "8") (pinfunction "-IN_8") (pintype "passive"))
    )
    (net (code "45") (name "Net-(U4-FB)") (class "Default")
      (node (ref "R22") (pin "1") (pinfunction "1_1") (pintype "passive"))
      (node (ref "R25") (pin "2") (pinfunction "2_2") (pintype "passive"))
      (node (ref "U4") (pin "2") (pinfunction "FB_2") (pintype "passive"))
    )
    (net (code "46") (name "Net-(U4-SW)") (class "Default")
      (node (ref "L1") (pin "2") (pinfunction "2_2") (pintype "passive"))
      (node (ref "U4") (pin "5") (pinfunction "SW_5") (pintype "passive"))
    )
    (net (code "47") (name "Net-(U4-VCC)") (class "Default")
      (node (ref "C14") (pin "1") (pinfunction "1_1") (pintype "passive"))
      (node (ref "R22") (pin "2") (pinfunction "2_2") (pintype "passive"))
      (node (ref "U4") (pin "6") (pinfunction "VCC_6") (pintype "passive"))
    )
    (net (code "48") (name "Net-(U5-ILIM)") (class "Default")
      (node (ref "R28") (pin "1") (pinfunction "1_1") (pintype "passive"))
      (node (ref "U5") (pin "7") (pinfunction "ILIM_7") (pintype "bidirectional"))
    )
    (net (code "49") (name "Net-(U6-CSET)") (class "Default")
      (node (ref "C23") (pin "1") (pinfunction "1_1") (pintype "passive"))
      (node (ref "U6") (pin "6") (pinfunction "CSET_6") (pintype "input"))
    )
    (net (code "50") (name "VDD_SERVO_PWR_IN") (class "Default")
      (node (ref "J4") (pin "6") (pinfunction "6_6") (pintype "passive"))
      (node (ref "R16") (pin "2") (pinfunction "2_2") (pintype "passive"))
      (node (ref "U5") (pin "1") (pinfunction "IN_1") (pintype "power_in"))
    )
    (net (code "51") (name "unconnected-(U1-NC-Pad3)") (class "Default")
      (node (ref "U1") (pin "3") (pinfunction "NC_3") (pintype "power_in+no_connect"))
    )
    (net (code "52") (name "unconnected-(U2-NC-Pad3)") (class "Default")
      (node (ref "U2") (pin "3") (pinfunction "NC_3") (pintype "power_in+no_connect"))
    )
    (net (code "53") (name "unconnected-(U3-CAS-Pad11)") (class "Default")
      (node (ref "U3") (pin "11") (pinfunction "CAS_11") (pintype "output+no_connect"))
    )
    (net (code "54") (name "unconnected-(U3-EN-Pad22)") (class "Default")
      (node (ref "U3") (pin "22") (pinfunction "EN_22") (pintype "passive+no_connect"))
    )
    (net (code "55") (name "unconnected-(U3-~{SHDN}-Pad23)") (class "Default")
      (node (ref "U3") (pin "23") (pinfunction "~{SHDN}_23") (pintype "passive+no_connect"))
    )
    (net (code "56") (name "unconnected-(U5-NC-Pad3)") (class "Default")
      (node (ref "U5") (pin "3") (pinfunction "NC_3") (pintype "power_in+no_connect"))
    )
    (net (code "57") (name "unconnected-(U5-~{FAULT}-Pad4)") (class "Default")
      (node (ref "U5") (pin "4") (pinfunction "~{FAULT}_4") (pintype "output+no_connect"))
    )
    (net (code "58") (name "unconnected-(U6-POR2-Pad3)") (class "Default")
      (node (ref "U6") (pin "3") (pinfunction "POR2_3") (pintype "output+no_connect"))
    )
    (net (code "59") (name "unconnected-(U6-VOUT2-Pad7)") (class "Default")
      (node (ref "U6") (pin "7") (pinfunction "VOUT2_7") (pintype "power_in+no_connect"))
    )
  )
)
